# drive_and_recover.net
KiCad netlist of a schematic drawn in EAGLE
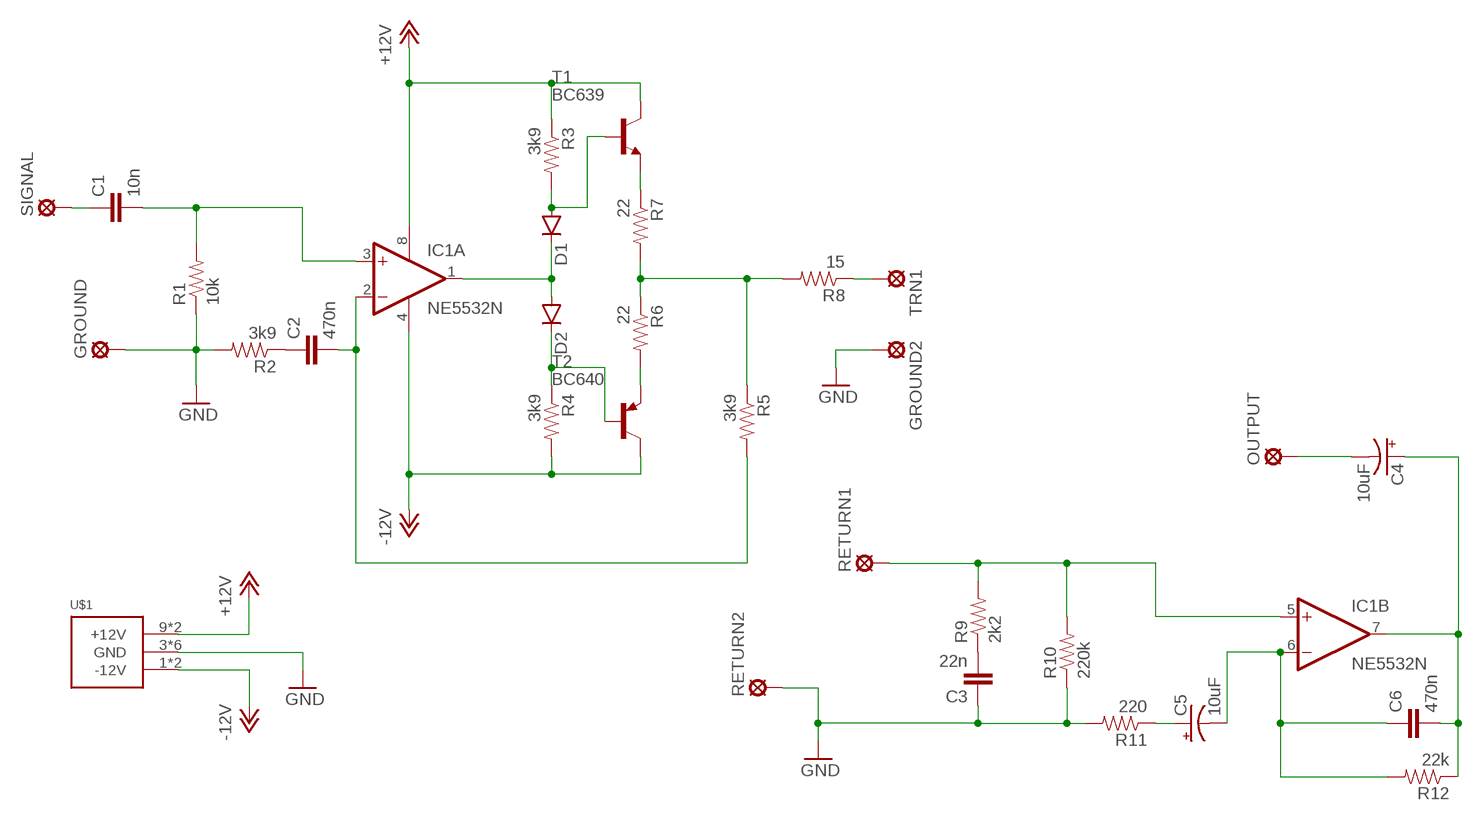
[diagram p0: schematic, sheet 1]

(export (version "E")
  (design (tool "Eeschema 10.0.6"))
  (components
    (comp (ref "C1")
      (value "10n")
      (footprint "eagle-import:CAP-PTH-SMALL")
      (libsource (lib "eagle-import") (part "CAPPTH"))
    )
    (comp (ref "C2")
      (value "470n")
      (footprint "eagle-import:CAP-PTH-SMALL")
      (libsource (lib "eagle-import") (part "CAPPTH"))
    )
    (comp (ref "C3")
      (value "22n")
      (footprint "eagle-import:CAP-PTH-SMALL")
      (libsource (lib "eagle-import") (part "CAPPTH"))
    )
    (comp (ref "C4")
      (value "10uF")
      (footprint "eagle-import:E2-5")
      (libsource (lib "eagle-import") (part "CPOL-USE2-5"))
    )
    (comp (ref "C5")
      (value "10uF")
      (footprint "eagle-import:E2-5")
      (libsource (lib "eagle-import") (part "CPOL-USE2-5"))
    )
    (comp (ref "C6")
      (value "470n")
      (footprint "eagle-import:CAP-PTH-SMALL")
      (libsource (lib "eagle-import") (part "CAPPTH"))
    )
    (comp (ref "D1")
      (value "DIODE1N4148")
      (footprint "eagle-import:DIODE-1N4148")
      (libsource (lib "eagle-import") (part "DIODE1N4148"))
    )
    (comp (ref "D2")
      (value "DIODE1N4148")
      (footprint "eagle-import:DIODE-1N4148")
      (libsource (lib "eagle-import") (part "DIODE1N4148"))
    )
    (comp (ref "GROUND")
      (value "LSP10")
      (footprint "eagle-import:LSP10")
      (libsource (lib "eagle-import") (part "LSP10"))
    )
    (comp (ref "GROUND2")
      (value "LSP10")
      (footprint "eagle-import:LSP10")
      (libsource (lib "eagle-import") (part "LSP10"))
    )
    (comp (ref "IC1")
      (value "NE5532N")
      (footprint "eagle-import:DIL08")
      (libsource (lib "eagle-import") (part "NE5532N"))
    )
    (comp (ref "OUTPUT")
      (value "LSP10")
      (footprint "eagle-import:LSP10")
      (libsource (lib "eagle-import") (part "LSP10"))
    )
    (comp (ref "R1")
      (value "10k")
      (footprint "eagle-import:AXIAL-0.4")
      (libsource (lib "eagle-import") (part "RESISTORPTH-1/4W"))
    )
    (comp (ref "R2")
      (value "3k9")
      (footprint "eagle-import:AXIAL-0.4")
      (libsource (lib "eagle-import") (part "RESISTORPTH-1/4W"))
    )
    (comp (ref "R3")
      (value "3k9")
      (footprint "eagle-import:AXIAL-0.4")
      (libsource (lib "eagle-import") (part "RESISTORPTH-1/4W"))
    )
    (comp (ref "R4")
      (value "3k9")
      (footprint "eagle-import:AXIAL-0.4")
      (libsource (lib "eagle-import") (part "RESISTORPTH-1/4W"))
    )
    (comp (ref "R5")
      (value "3k9")
      (footprint "eagle-import:AXIAL-0.4")
      (libsource (lib "eagle-import") (part "RESISTORPTH-1/4W"))
    )
    (comp (ref "R6")
      (value "22")
      (footprint "eagle-import:AXIAL-0.4")
      (libsource (lib "eagle-import") (part "RESISTORPTH-1/4W"))
    )
    (comp (ref "R7")
      (value "22")
      (footprint "eagle-import:AXIAL-0.4")
      (libsource (lib "eagle-import") (part "RESISTORPTH-1/4W"))
    )
    (comp (ref "R8")
      (value "15")
      (footprint "eagle-import:AXIAL-0.4")
      (libsource (lib "eagle-import") (part "RESISTORPTH-1/4W"))
    )
    (comp (ref "R9")
      (value "2k2")
      (footprint "eagle-import:AXIAL-0.4")
      (libsource (lib "eagle-import") (part "RESISTORPTH-1/4W"))
    )
    (comp (ref "R10")
      (value "220k")
      (footprint "eagle-import:AXIAL-0.4")
      (libsource (lib "eagle-import") (part "RESISTORPTH-1/4W"))
    )
    (comp (ref "R11")
      (value "220")
      (footprint "eagle-import:AXIAL-0.4")
      (libsource (lib "eagle-import") (part "RESISTORPTH-1/4W"))
    )
    (comp (ref "R12")
      (value "22k")
      (footprint "eagle-import:AXIAL-0.4")
      (libsource (lib "eagle-import") (part "RESISTORPTH-1/4W"))
    )
    (comp (ref "RETURN1")
      (value "LSP10")
      (footprint "eagle-import:LSP10")
      (libsource (lib "eagle-import") (part "LSP10"))
    )
    (comp (ref "RETURN2")
      (value "LSP10")
      (footprint "eagle-import:LSP10")
      (libsource (lib "eagle-import") (part "LSP10"))
    )
    (comp (ref "SIGNAL")
      (value "LSP10")
      (footprint "eagle-import:LSP10")
      (libsource (lib "eagle-import") (part "LSP10"))
    )
    (comp (ref "T1")
      (value "BC639")
      (footprint "eagle-import:TO92-ECB")
      (libsource (lib "eagle-import") (part "-NPN-TO92-ECBBC639"))
    )
    (comp (ref "T2")
      (value "BC640")
      (footprint "eagle-import:TO92-BCE")
      (libsource (lib "eagle-import") (part "-PNP-TO92-BCEBC640"))
    )
    (comp (ref "TRN1")
      (value "LSP10")
      (footprint "eagle-import:LSP10")
      (libsource (lib "eagle-import") (part "LSP10"))
    )
    (comp (ref "U$1")
      (value "POWER_SIMPLE16")
      (footprint "eagle-import:POWER_16")
      (libsource (lib "eagle-import") (part "POWER_SIMPLE16"))
    )
  )
  (nets
    (net (code "1") (name "+12V") (class "Default")
      (node (ref "IC1") (pin "8") (pinfunction "V+_8") (pintype "power_in"))
      (node (ref "R3") (pin "P$1") (pinfunction "1_P$1") (pintype "passive"))
      (node (ref "T1") (pin "C") (pinfunction "C_C") (pintype "passive"))
      (node (ref "U$1") (pin "10") (pinfunction "+12V_10") (pintype "bidirectional"))
      (node (ref "U$1") (pin "9") (pinfunction "+12V_9") (pintype "bidirectional"))
    )
    (net (code "2") (name "-12V") (class "Default")
      (node (ref "IC1") (pin "4") (pinfunction "V-_4") (pintype "power_in"))
      (node (ref "R4") (pin "P$2") (pinfunction "2_P$2") (pintype "passive"))
      (node (ref "T2") (pin "C") (pinfunction "C_C") (pintype "passive"))
      (node (ref "U$1") (pin "1") (pinfunction "-12V_1") (pintype "bidirectional"))
      (node (ref "U$1") (pin "2") (pinfunction "-12V_2") (pintype "bidirectional"))
    )
    (net (code "3") (name "GND") (class "Default")
      (node (ref "C3") (pin "1") (pinfunction "1_1") (pintype "passive"))
      (node (ref "GROUND") (pin "MP") (pinfunction "MP_MP") (pintype "passive"))
      (node (ref "GROUND2") (pin "MP") (pinfunction "MP_MP") (pintype "passive"))
      (node (ref "R1") (pin "P$1") (pinfunction "1_P$1") (pintype "passive"))
      (node (ref "R10") (pin "P$1") (pinfunction "1_P$1") (pintype "passive"))
      (node (ref "R11") (pin "P$2") (pinfunction "2_P$2") (pintype "passive"))
      (node (ref "R2") (pin "P$2") (pinfunction "2_P$2") (pintype "passive"))
      (node (ref "RETURN2") (pin "MP") (pinfunction "MP_MP") (pintype "passive"))
      (node (ref "U$1") (pin "3") (pinfunction "GND_3") (pintype "bidirectional"))
      (node (ref "U$1") (pin "4") (pinfunction "GND_4") (pintype "bidirectional"))
      (node (ref "U$1") (pin "5") (pinfunction "GND_5") (pintype "bidirectional"))
      (node (ref "U$1") (pin "6") (pinfunction "GND_6") (pintype "bidirectional"))
      (node (ref "U$1") (pin "7") (pinfunction "GND_7") (pintype "bidirectional"))
      (node (ref "U$1") (pin "8") (pinfunction "GND_8") (pintype "bidirectional"))
    )
    (net (code "4") (name "Net-(C1-Pad1)") (class "Default")
      (node (ref "C1") (pin "1") (pinfunction "1_1") (pintype "passive"))
      (node (ref "SIGNAL") (pin "MP") (pinfunction "MP_MP") (pintype "passive"))
    )
    (net (code "5") (name "Net-(C4-Pad-)") (class "Default")
      (node (ref "C4") (pin "-") (pinfunction "-_-") (pintype "passive"))
      (node (ref "OUTPUT") (pin "MP") (pinfunction "MP_MP") (pintype "passive"))
    )
    (net (code "6") (name "Net-(IC1A-+IN)") (class "Default")
      (node (ref "C1") (pin "2") (pinfunction "2_2") (pintype "passive"))
      (node (ref "IC1") (pin "3") (pinfunction "+IN_3") (pintype "input"))
      (node (ref "R1") (pin "P$2") (pinfunction "2_P$2") (pintype "passive"))
    )
    (net (code "7") (name "Net-(IC1A--IN)") (class "Default")
      (node (ref "C2") (pin "2") (pinfunction "2_2") (pintype "passive"))
      (node (ref "IC1") (pin "2") (pinfunction "-IN_2") (pintype "input"))
      (node (ref "R5") (pin "P$2") (pinfunction "2_P$2") (pintype "passive"))
    )
    (net (code "8") (name "Net-(IC1A-OUT)") (class "Default")
      (node (ref "D1") (pin "C") (pinfunction "C_C") (pintype "passive"))
      (node (ref "D2") (pin "A") (pinfunction "A_A") (pintype "passive"))
      (node (ref "IC1") (pin "1") (pinfunction "OUT_1") (pintype "output"))
    )
    (net (code "9") (name "Net-(IC1B-+IN)") (class "Default")
      (node (ref "IC1") (pin "5") (pinfunction "+IN_5") (pintype "input"))
      (node (ref "R10") (pin "P$2") (pinfunction "2_P$2") (pintype "passive"))
      (node (ref "R9") (pin "P$2") (pinfunction "2_P$2") (pintype "passive"))
      (node (ref "RETURN1") (pin "MP") (pinfunction "MP_MP") (pintype "passive"))
    )
    (net (code "10") (name "Net-(IC1B--IN)") (class "Default")
      (node (ref "C5") (pin "-") (pinfunction "-_-") (pintype "passive"))
      (node (ref "C6") (pin "1") (pinfunction "1_1") (pintype "passive"))
      (node (ref "IC1") (pin "6") (pinfunction "-IN_6") (pintype "input"))
      (node (ref "R12") (pin "P$2") (pinfunction "2_P$2") (pintype "passive"))
    )
    (net (code "11") (name "Net-(IC1B-OUT)") (class "Default")
      (node (ref "C4") (pin "+") (pinfunction "+_+") (pintype "passive"))
      (node (ref "C6") (pin "2") (pinfunction "2_2") (pintype "passive"))
      (node (ref "IC1") (pin "7") (pinfunction "OUT_7") (pintype "output"))
      (node (ref "R12") (pin "P$1") (pinfunction "1_P$1") (pintype "passive"))
    )
    (net (code "12") (name "Net-(R2-1)") (class "Default")
      (node (ref "C2") (pin "1") (pinfunction "1_1") (pintype "passive"))
      (node (ref "R2") (pin "P$1") (pinfunction "1_P$1") (pintype "passive"))
    )
    (net (code "13") (name "Net-(R3-2)") (class "Default")
      (node (ref "D1") (pin "A") (pinfunction "A_A") (pintype "passive"))
      (node (ref "R3") (pin "P$2") (pinfunction "2_P$2") (pintype "passive"))
      (node (ref "T1") (pin "B") (pinfunction "B_B") (pintype "passive"))
    )
    (net (code "14") (name "Net-(R4-1)") (class "Default")
      (node (ref "D2") (pin "C") (pinfunction "C_C") (pintype "passive"))
      (node (ref "R4") (pin "P$1") (pinfunction "1_P$1") (pintype "passive"))
      (node (ref "T2") (pin "B") (pinfunction "B_B") (pintype "passive"))
    )
    (net (code "15") (name "Net-(R5-1)") (class "Default")
      (node (ref "R5") (pin "P$1") (pinfunction "1_P$1") (pintype "passive"))
      (node (ref "R6") (pin "P$1") (pinfunction "1_P$1") (pintype "passive"))
      (node (ref "R7") (pin "P$2") (pinfunction "2_P$2") (pintype "passive"))
      (node (ref "R8") (pin "P$2") (pinfunction "2_P$2") (pintype "passive"))
    )
    (net (code "16") (name "Net-(R6-2)") (class "Default")
      (node (ref "R6") (pin "P$2") (pinfunction "2_P$2") (pintype "passive"))
      (node (ref "T2") (pin "E") (pinfunction "E_E") (pintype "passive"))
    )
    (net (code "17") (name "Net-(R7-1)") (class "Default")
      (node (ref "R7") (pin "P$1") (pinfunction "1_P$1") (pintype "passive"))
      (node (ref "T1") (pin "E") (pinfunction "E_E") (pintype "passive"))
    )
    (net (code "18") (name "Net-(R8-1)") (class "Default")
      (node (ref "R8") (pin "P$1") (pinfunction "1_P$1") (pintype "passive"))
      (node (ref "TRN1") (pin "MP") (pinfunction "MP_MP") (pintype "passive"))
    )
    (net (code "19") (name "Net-(R9-1)") (class "Default")
      (node (ref "C3") (pin "2") (pinfunction "2_2") (pintype "passive"))
      (node (ref "R9") (pin "P$1") (pinfunction "1_P$1") (pintype "passive"))
    )
    (net (code "20") (name "Net-(R11-1)") (class "Default")
      (node (ref "C5") (pin "+") (pinfunction "+_+") (pintype "passive"))
      (node (ref "R11") (pin "P$1") (pinfunction "1_P$1") (pintype "passive"))
    )
  )
)
